# ps.net
KiCad netlist of a schematic drawn in EAGLE
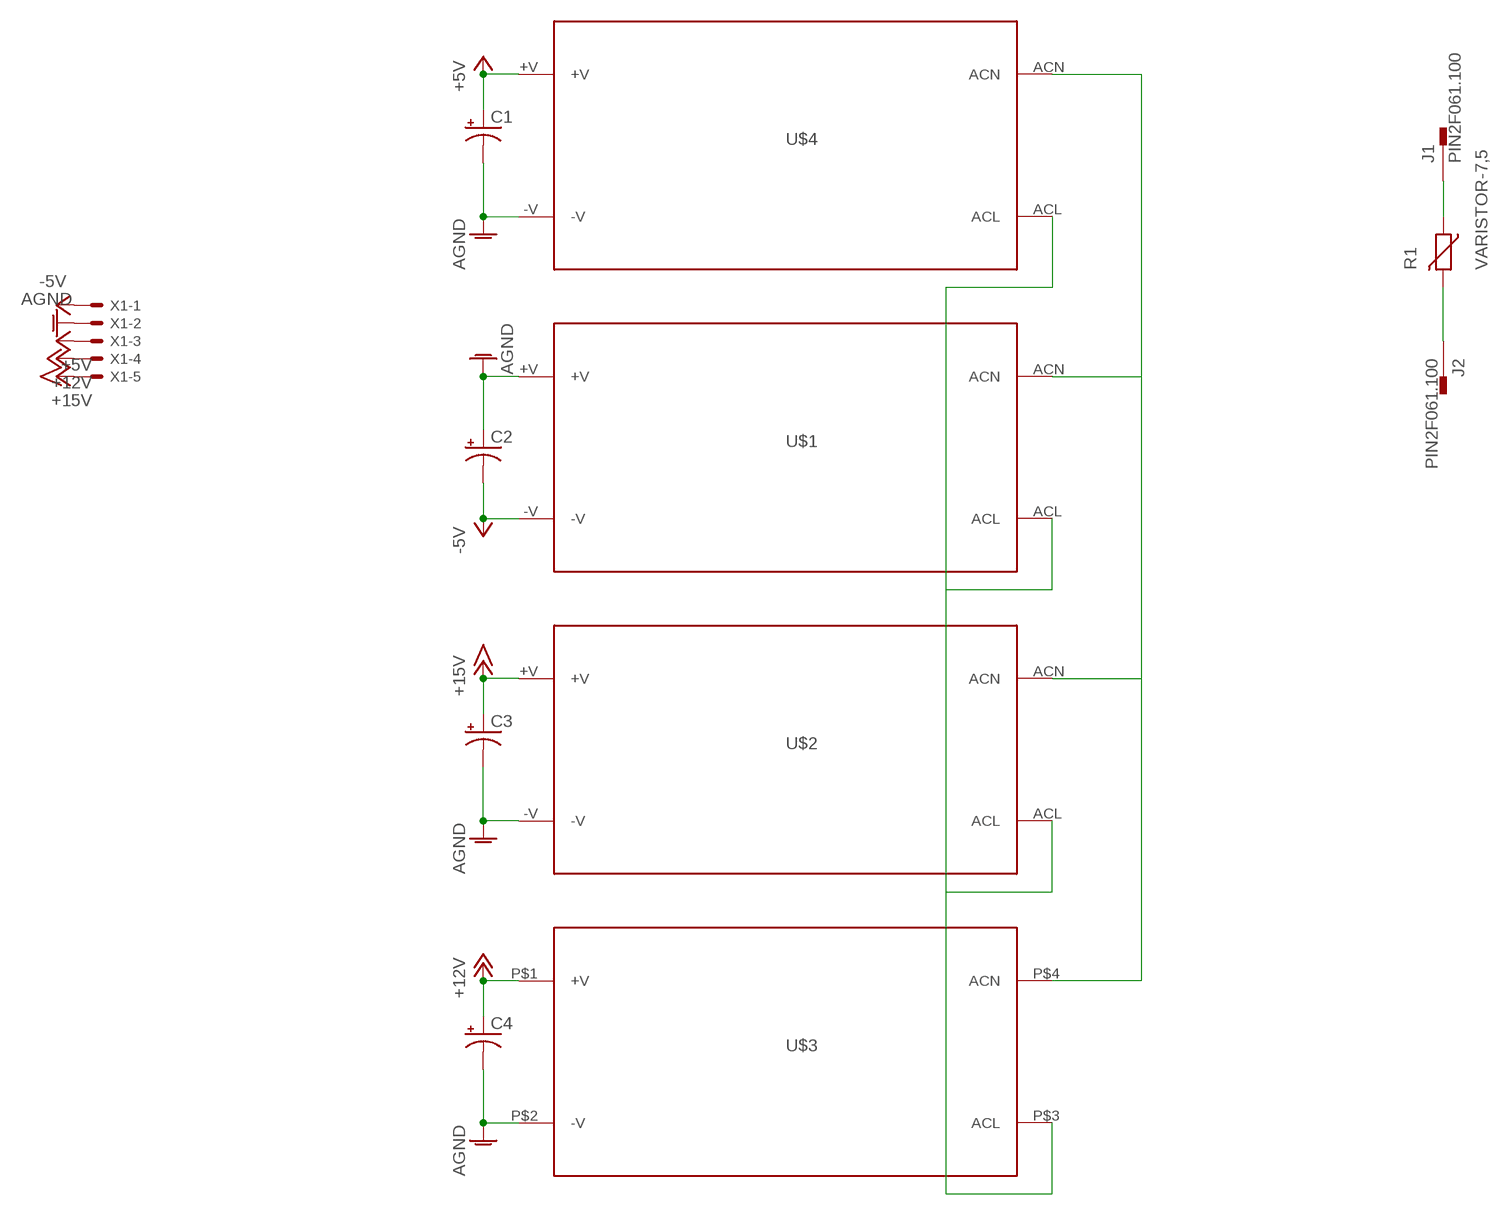
[diagram p0: schematic, sheet 1]

(export (version "E")
  (design (tool "Eeschema 10.0.6"))
  (components
    (comp (ref "C1")
      (value "CPOL-USE10-22.5")
      (footprint "eagle-import:EB22,5D")
      (libsource (lib "eagle-import") (part "CPOL-USE10-22.5"))
    )
    (comp (ref "C2")
      (value "CPOL-USE10-22.5")
      (footprint "eagle-import:EB22,5D")
      (libsource (lib "eagle-import") (part "CPOL-USE10-22.5"))
    )
    (comp (ref "C3")
      (value "CPOL-USE10-22.5")
      (footprint "eagle-import:EB22,5D")
      (libsource (lib "eagle-import") (part "CPOL-USE10-22.5"))
    )
    (comp (ref "C4")
      (value "CPOL-USE10-22.5")
      (footprint "eagle-import:EB22,5D")
      (libsource (lib "eagle-import") (part "CPOL-USE10-22.5"))
    )
    (comp (ref "J1")
      (value "PIN2F061.100")
      (footprint "eagle-import:F061.100")
      (libsource (lib "eagle-import") (part "PIN2F061.100"))
    )
    (comp (ref "J2")
      (value "PIN2F061.100")
      (footprint "eagle-import:F061.100")
      (libsource (lib "eagle-import") (part "PIN2F061.100"))
    )
    (comp (ref "R1")
      (value "VARISTOR-7,5")
      (footprint "eagle-import:R-7,5")
      (libsource (lib "eagle-import") (part "VARISTOR-7,5"))
    )
    (comp (ref "U$1")
      (value "IRM-30-5")
      (footprint "eagle-import:IRM-30-15")
      (libsource (lib "eagle-import") (part "IRM-30-5"))
    )
    (comp (ref "U$2")
      (value "IRM-30-15")
      (footprint "eagle-import:IRM-30-15")
      (libsource (lib "eagle-import") (part "IRM-30-15"))
    )
    (comp (ref "U$3")
      (value "IRM-60-12")
      (footprint "eagle-import:IRM-60-12")
      (libsource (lib "eagle-import") (part "IRM-60-12"))
    )
    (comp (ref "U$4")
      (value "IRM-30-5")
      (footprint "eagle-import:IRM-30-15")
      (libsource (lib "eagle-import") (part "IRM-30-5"))
    )
    (comp (ref "X1")
      (value "KK-156-5")
      (footprint "eagle-import:KK-156-5")
      (libsource (lib "eagle-import") (part "KK-156-5"))
    )
  )
  (nets
    (net (code "1") (name "+5V") (class "Default")
      (node (ref "C1") (pin "+") (pinfunction "+_+") (pintype "passive"))
      (node (ref "U$4") (pin "+V") (pinfunction "+V_+V") (pintype "bidirectional"))
      (node (ref "X1") (pin "3") (pinfunction "S_3") (pintype "passive"))
    )
    (net (code "2") (name "+12V") (class "Default")
      (node (ref "C4") (pin "+") (pinfunction "+_+") (pintype "passive"))
      (node (ref "U$3") (pin "P$1") (pinfunction "+V_P$1") (pintype "bidirectional"))
      (node (ref "X1") (pin "4") (pinfunction "S_4") (pintype "passive"))
    )
    (net (code "3") (name "+15V") (class "Default")
      (node (ref "C3") (pin "+") (pinfunction "+_+") (pintype "passive"))
      (node (ref "U$2") (pin "+V") (pinfunction "+V_+V") (pintype "bidirectional"))
      (node (ref "X1") (pin "5") (pinfunction "S_5") (pintype "passive"))
    )
    (net (code "4") (name "-5V") (class "Default")
      (node (ref "C2") (pin "-") (pinfunction "-_-") (pintype "passive"))
      (node (ref "U$1") (pin "-V") (pinfunction "-V_-V") (pintype "bidirectional"))
      (node (ref "X1") (pin "1") (pinfunction "S_1") (pintype "passive"))
    )
    (net (code "5") (name "/ACL") (class "Default")
      (node (ref "J1") (pin "A1") (pinfunction "1_A1") (pintype "passive"))
      (node (ref "J1") (pin "A2") (pinfunction "1_A2") (pintype "passive"))
      (node (ref "R1") (pin "1") (pinfunction "1_1") (pintype "passive"))
      (node (ref "U$1") (pin "ACL") (pinfunction "ACL_ACL") (pintype "bidirectional"))
      (node (ref "U$2") (pin "ACL") (pinfunction "ACL_ACL") (pintype "bidirectional"))
      (node (ref "U$3") (pin "P$3") (pinfunction "ACL_P$3") (pintype "bidirectional"))
      (node (ref "U$4") (pin "ACL") (pinfunction "ACL_ACL") (pintype "bidirectional"))
    )
    (net (code "6") (name "/ACN") (class "Default")
      (node (ref "J2") (pin "A1") (pinfunction "1_A1") (pintype "passive"))
      (node (ref "J2") (pin "A2") (pinfunction "1_A2") (pintype "passive"))
      (node (ref "R1") (pin "2") (pinfunction "2_2") (pintype "passive"))
      (node (ref "U$1") (pin "ACN") (pinfunction "ACN_ACN") (pintype "bidirectional"))
      (node (ref "U$2") (pin "ACN") (pinfunction "ACN_ACN") (pintype "bidirectional"))
      (node (ref "U$3") (pin "P$4") (pinfunction "ACN_P$4") (pintype "bidirectional"))
      (node (ref "U$4") (pin "ACN") (pinfunction "ACN_ACN") (pintype "bidirectional"))
    )
    (net (code "7") (name "AGND") (class "Default")
      (node (ref "C1") (pin "-") (pinfunction "-_-") (pintype "passive"))
      (node (ref "C2") (pin "+") (pinfunction "+_+") (pintype "passive"))
      (node (ref "C3") (pin "-") (pinfunction "-_-") (pintype "passive"))
      (node (ref "C4") (pin "-") (pinfunction "-_-") (pintype "passive"))
      (node (ref "U$1") (pin "+V") (pinfunction "+V_+V") (pintype "bidirectional"))
      (node (ref "U$2") (pin "-V") (pinfunction "-V_-V") (pintype "bidirectional"))
      (node (ref "U$3") (pin "P$2") (pinfunction "-V_P$2") (pintype "bidirectional"))
      (node (ref "U$4") (pin "-V") (pinfunction "-V_-V") (pintype "bidirectional"))
      (node (ref "X1") (pin "2") (pinfunction "S_2") (pintype "passive"))
    )
  )
)
